# Player_Module.net
KiCad netlist of a schematic drawn in EAGLE
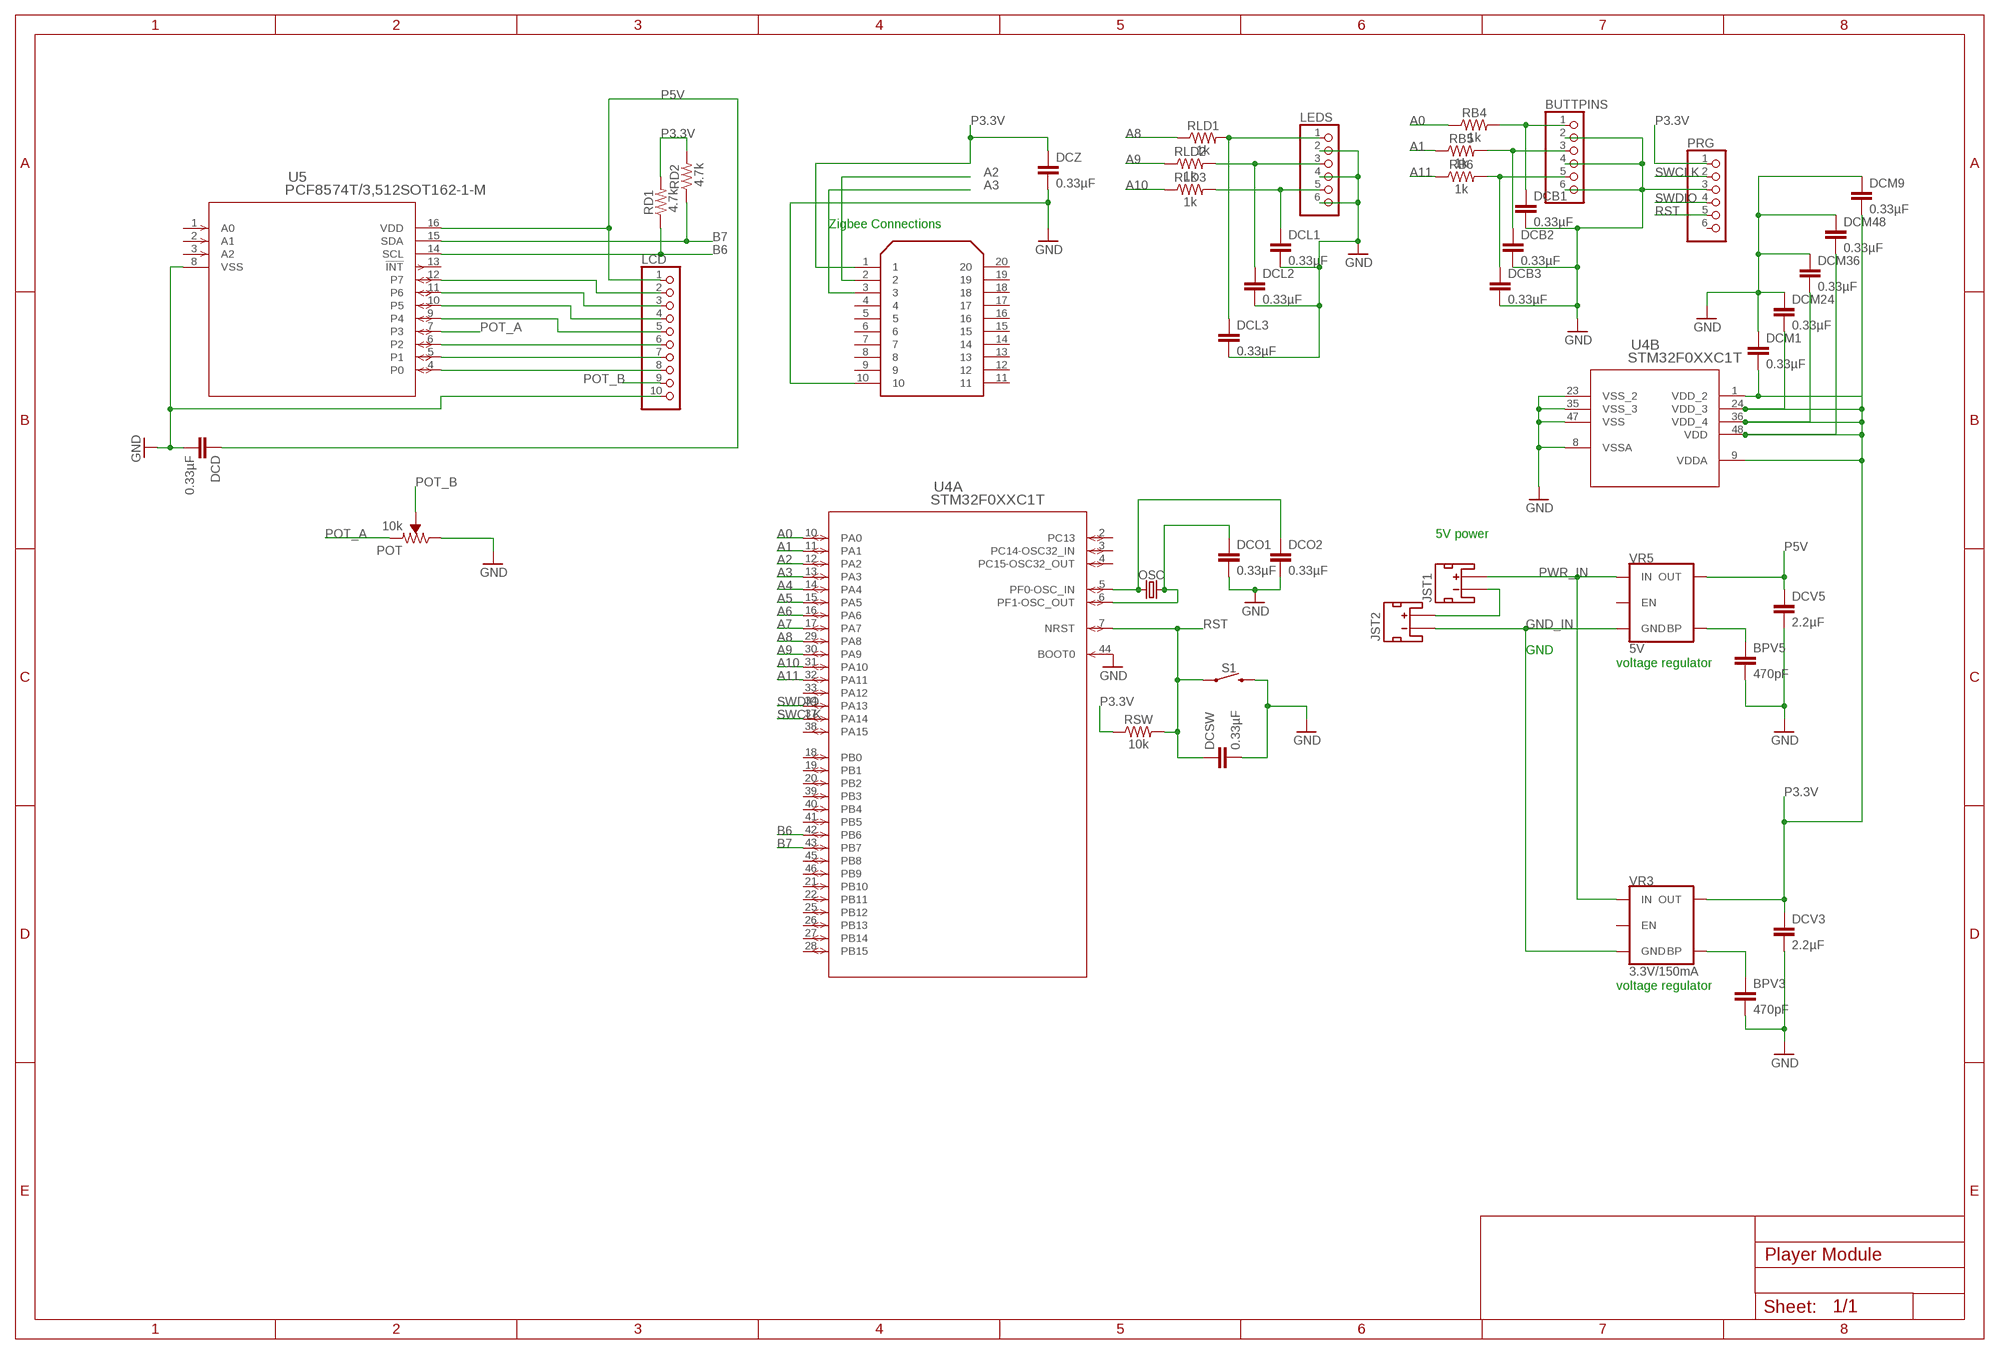
[diagram p0: schematic, sheet 1]

(export (version "E")
  (design (tool "Eeschema 10.0.6"))
  (components
    (comp (ref "BPV3")
      (value "470pF")
      (footprint "eagle-import:0805")
      (libsource (lib "eagle-import") (part "0.33UF/330NF-0805-50V-10%"))
    )
    (comp (ref "BPV5")
      (value "470pF")
      (footprint "eagle-import:0805")
      (libsource (lib "eagle-import") (part "0.33UF/330NF-0805-50V-10%"))
    )
    (comp (ref "BUTTPINS")
      (value "PINHD-1X6")
      (footprint "eagle-import:1X06")
      (libsource (lib "eagle-import") (part "PINHD-1X6"))
    )
    (comp (ref "DCB1")
      (value "0.33µF")
      (footprint "eagle-import:0805")
      (libsource (lib "eagle-import") (part "0.33UF/330NF-0805-50V-10%"))
    )
    (comp (ref "DCB2")
      (value "0.33µF")
      (footprint "eagle-import:0805")
      (libsource (lib "eagle-import") (part "0.33UF/330NF-0805-50V-10%"))
    )
    (comp (ref "DCB3")
      (value "0.33µF")
      (footprint "eagle-import:0805")
      (libsource (lib "eagle-import") (part "0.33UF/330NF-0805-50V-10%"))
    )
    (comp (ref "DCD")
      (value "0.33µF")
      (footprint "eagle-import:0805")
      (libsource (lib "eagle-import") (part "0.33UF/330NF-0805-50V-10%"))
    )
    (comp (ref "DCL1")
      (value "0.33µF")
      (footprint "eagle-import:0805")
      (libsource (lib "eagle-import") (part "0.33UF/330NF-0805-50V-10%"))
    )
    (comp (ref "DCL2")
      (value "0.33µF")
      (footprint "eagle-import:0805")
      (libsource (lib "eagle-import") (part "0.33UF/330NF-0805-50V-10%"))
    )
    (comp (ref "DCL3")
      (value "0.33µF")
      (footprint "eagle-import:0805")
      (libsource (lib "eagle-import") (part "0.33UF/330NF-0805-50V-10%"))
    )
    (comp (ref "DCM1")
      (value "0.33µF")
      (footprint "eagle-import:0805")
      (libsource (lib "eagle-import") (part "0.33UF/330NF-0805-50V-10%"))
    )
    (comp (ref "DCM9")
      (value "0.33µF")
      (footprint "eagle-import:0805")
      (libsource (lib "eagle-import") (part "0.33UF/330NF-0805-50V-10%"))
    )
    (comp (ref "DCM24")
      (value "0.33µF")
      (footprint "eagle-import:0805")
      (libsource (lib "eagle-import") (part "0.33UF/330NF-0805-50V-10%"))
    )
    (comp (ref "DCM36")
      (value "0.33µF")
      (footprint "eagle-import:0805")
      (libsource (lib "eagle-import") (part "0.33UF/330NF-0805-50V-10%"))
    )
    (comp (ref "DCM48")
      (value "0.33µF")
      (footprint "eagle-import:0805")
      (libsource (lib "eagle-import") (part "0.33UF/330NF-0805-50V-10%"))
    )
    (comp (ref "DCO1")
      (value "0.33µF")
      (footprint "eagle-import:0805")
      (libsource (lib "eagle-import") (part "0.33UF/330NF-0805-50V-10%"))
    )
    (comp (ref "DCO2")
      (value "0.33µF")
      (footprint "eagle-import:0805")
      (libsource (lib "eagle-import") (part "0.33UF/330NF-0805-50V-10%"))
    )
    (comp (ref "DCSW")
      (value "0.33µF")
      (footprint "eagle-import:0805")
      (libsource (lib "eagle-import") (part "0.33UF/330NF-0805-50V-10%"))
    )
    (comp (ref "DCV3")
      (value "2.2µF")
      (footprint "eagle-import:0805")
      (libsource (lib "eagle-import") (part "0.33UF/330NF-0805-50V-10%"))
    )
    (comp (ref "DCV5")
      (value "2.2µF")
      (footprint "eagle-import:0805")
      (libsource (lib "eagle-import") (part "0.33UF/330NF-0805-50V-10%"))
    )
    (comp (ref "DCZ")
      (value "0.33µF")
      (footprint "eagle-import:0805")
      (libsource (lib "eagle-import") (part "0.33UF/330NF-0805-50V-10%"))
    )
    (comp (ref "JST1")
      (value "JST_2MM_MALE")
      (footprint "eagle-import:JST-2-SMD")
      (libsource (lib "eagle-import") (part "JST_2MM_MALE"))
    )
    (comp (ref "JST2")
      (value "JST_2MM_MALE")
      (footprint "eagle-import:JST-2-SMD")
      (libsource (lib "eagle-import") (part "JST_2MM_MALE"))
    )
    (comp (ref "LCD")
      (value "PINHD-1X10")
      (footprint "eagle-import:1X10")
      (libsource (lib "eagle-import") (part "PINHD-1X10"))
    )
    (comp (ref "LEDS")
      (value "PINHD-1X6")
      (footprint "eagle-import:1X06")
      (libsource (lib "eagle-import") (part "PINHD-1X6"))
    )
    (comp (ref "OSC")
      (value "CRYSTALPTH-HC49US")
      (footprint "eagle-import:HC49US")
      (libsource (lib "eagle-import") (part "CRYSTALPTH-HC49US"))
    )
    (comp (ref "POT")
      (value "10k")
      (footprint "eagle-import:TRIMPOT-PTH-3386U")
      (libsource (lib "eagle-import") (part "TRIMPOT-PTH-10MM-KNOB-1/2W-10%"))
    )
    (comp (ref "PRG")
      (value "PINHD-1X6")
      (footprint "eagle-import:1X06")
      (libsource (lib "eagle-import") (part "PINHD-1X6"))
    )
    (comp (ref "RB4")
      (value "1k")
      (footprint "eagle-import:0805")
      (libsource (lib "eagle-import") (part "RESISTOR0805"))
    )
    (comp (ref "RB5")
      (value "1k")
      (footprint "eagle-import:0805")
      (libsource (lib "eagle-import") (part "RESISTOR0805"))
    )
    (comp (ref "RB6")
      (value "1k")
      (footprint "eagle-import:0805")
      (libsource (lib "eagle-import") (part "RESISTOR0805"))
    )
    (comp (ref "RD1")
      (value "4.7k")
      (footprint "eagle-import:0805")
      (libsource (lib "eagle-import") (part "RESISTOR0805"))
    )
    (comp (ref "RD2")
      (value "4.7k")
      (footprint "eagle-import:0805")
      (libsource (lib "eagle-import") (part "RESISTOR0805"))
    )
    (comp (ref "RLD1")
      (value "1k")
      (footprint "eagle-import:0805")
      (libsource (lib "eagle-import") (part "RESISTOR0805"))
    )
    (comp (ref "RLD2")
      (value "1k")
      (footprint "eagle-import:0805")
      (libsource (lib "eagle-import") (part "RESISTOR0805"))
    )
    (comp (ref "RLD3")
      (value "1k")
      (footprint "eagle-import:0805")
      (libsource (lib "eagle-import") (part "RESISTOR0805"))
    )
    (comp (ref "RSW")
      (value "10k")
      (footprint "eagle-import:0805")
      (libsource (lib "eagle-import") (part "RESISTOR0805"))
    )
    (comp (ref "S1")
      (value "MOMENTARY-SWITCH-SPST-SMD-5.2MM")
      (footprint "eagle-import:TACTILE_SWITCH_SMD_5.2MM")
      (libsource (lib "eagle-import") (part "MOMENTARY-SWITCH-SPST-SMD-5.2MM"))
    )
    (comp (ref "U$1")
      (value "XB24-BPIT-004")
      (footprint "eagle-import:DIP-20")
      (fields (field (name "MF") "Digi International"))
      (libsource (lib "eagle-import") (part "XB24-BPIT-004"))
    )
    (comp (ref "U4")
      (value "STM32F0XXC1T")
      (footprint "eagle-import:LQFP48-7X7MM")
      (fields (field (name "MANUFACTURER_PART_NUMBER") "stm32f0xxc1t"))
      (libsource (lib "eagle-import") (part "STM32F0XXC1T"))
    )
    (comp (ref "U5")
      (value "PCF8574T/3,512SOT162-1-M")
      (footprint "eagle-import:SOT162-1-M")
      (fields (field (name "MANUFACTURER_PART_NUMBER") "PCF8574T3512"))
      (libsource (lib "eagle-import") (part "PCF8574T/3,512SOT162-1-M"))
    )
    (comp (ref "VR3")
      (value "3.3V/150mA")
      (footprint "eagle-import:SOT23-5")
      (libsource (lib "eagle-import") (part "V_REG_MIC52053.3V"))
    )
    (comp (ref "VR5")
      (value "5V")
      (footprint "eagle-import:SOT23-5")
      (libsource (lib "eagle-import") (part "V_REG_MIC52055V"))
    )
  )
  (nets
    (net (code "1") (name "/A0") (class "Default")
      (node (ref "RB4") (pin "1") (pinfunction "1_1") (pintype "passive"))
      (node (ref "U4") (pin "10") (pinfunction "PA0_10") (pintype "bidirectional"))
    )
    (net (code "2") (name "/A1") (class "Default")
      (node (ref "RB5") (pin "1") (pinfunction "1_1") (pintype "passive"))
      (node (ref "U4") (pin "11") (pinfunction "PA1_11") (pintype "bidirectional"))
    )
    (net (code "3") (name "/A2") (class "Default")
      (node (ref "U$1") (pin "2") (pinfunction "2_2") (pintype "bidirectional"))
      (node (ref "U4") (pin "12") (pinfunction "PA2_12") (pintype "bidirectional"))
    )
    (net (code "4") (name "/A3") (class "Default")
      (node (ref "U$1") (pin "3") (pinfunction "3_3") (pintype "bidirectional"))
      (node (ref "U4") (pin "13") (pinfunction "PA3_13") (pintype "bidirectional"))
    )
    (net (code "5") (name "/A4") (class "Default")
      (node (ref "U4") (pin "14") (pinfunction "PA4_14") (pintype "bidirectional"))
    )
    (net (code "6") (name "/A5") (class "Default")
      (node (ref "U4") (pin "15") (pinfunction "PA5_15") (pintype "bidirectional"))
    )
    (net (code "7") (name "/A6") (class "Default")
      (node (ref "U4") (pin "16") (pinfunction "PA6_16") (pintype "bidirectional"))
    )
    (net (code "8") (name "/A7") (class "Default")
      (node (ref "U4") (pin "17") (pinfunction "PA7_17") (pintype "bidirectional"))
    )
    (net (code "9") (name "/A8") (class "Default")
      (node (ref "RLD1") (pin "1") (pinfunction "1_1") (pintype "passive"))
      (node (ref "U4") (pin "29") (pinfunction "PA8_29") (pintype "bidirectional"))
    )
    (net (code "10") (name "/A9") (class "Default")
      (node (ref "RLD2") (pin "1") (pinfunction "1_1") (pintype "passive"))
      (node (ref "U4") (pin "30") (pinfunction "PA9_30") (pintype "bidirectional"))
    )
    (net (code "11") (name "/A10") (class "Default")
      (node (ref "RLD3") (pin "1") (pinfunction "1_1") (pintype "passive"))
      (node (ref "U4") (pin "31") (pinfunction "PA10_31") (pintype "bidirectional"))
    )
    (net (code "12") (name "/A11") (class "Default")
      (node (ref "RB6") (pin "1") (pinfunction "1_1") (pintype "passive"))
      (node (ref "U4") (pin "32") (pinfunction "PA11_32") (pintype "bidirectional"))
    )
    (net (code "13") (name "/B6") (class "Default")
      (node (ref "RD1") (pin "1") (pinfunction "1_1") (pintype "passive"))
      (node (ref "U4") (pin "42") (pinfunction "PB6_42") (pintype "bidirectional"))
      (node (ref "U5") (pin "14") (pinfunction "SCL_14") (pintype "passive"))
    )
    (net (code "14") (name "/B7") (class "Default")
      (node (ref "RD2") (pin "1") (pinfunction "1_1") (pintype "passive"))
      (node (ref "U4") (pin "43") (pinfunction "PB7_43") (pintype "bidirectional"))
      (node (ref "U5") (pin "15") (pinfunction "SDA_15") (pintype "passive"))
    )
    (net (code "15") (name "/GND_IN") (class "Default")
      (node (ref "JST2") (pin "1") (pinfunction "-_1") (pintype "bidirectional"))
      (node (ref "VR3") (pin "2") (pinfunction "GND_2") (pintype "input"))
      (node (ref "VR5") (pin "2") (pinfunction "GND_2") (pintype "input"))
    )
    (net (code "16") (name "/P3.3V") (class "Default")
      (node (ref "DCM1") (pin "2") (pinfunction "2_2") (pintype "passive"))
      (node (ref "DCM24") (pin "2") (pinfunction "2_2") (pintype "passive"))
      (node (ref "DCM36") (pin "2") (pinfunction "2_2") (pintype "passive"))
      (node (ref "DCM48") (pin "2") (pinfunction "2_2") (pintype "passive"))
      (node (ref "DCM9") (pin "2") (pinfunction "2_2") (pintype "passive"))
      (node (ref "DCV3") (pin "1") (pinfunction "1_1") (pintype "passive"))
      (node (ref "DCZ") (pin "1") (pinfunction "1_1") (pintype "passive"))
      (node (ref "PRG") (pin "1") (pinfunction "1_1") (pintype "passive"))
      (node (ref "RD1") (pin "2") (pinfunction "2_2") (pintype "passive"))
      (node (ref "RD2") (pin "2") (pinfunction "2_2") (pintype "passive"))
      (node (ref "RSW") (pin "1") (pinfunction "1_1") (pintype "passive"))
      (node (ref "U$1") (pin "1") (pinfunction "1_1") (pintype "bidirectional"))
      (node (ref "U4") (pin "1") (pinfunction "VDD_2_1") (pintype "power_in"))
      (node (ref "U4") (pin "24") (pinfunction "VDD_3_24") (pintype "power_in"))
      (node (ref "U4") (pin "36") (pinfunction "VDD_4_36") (pintype "power_in"))
      (node (ref "U4") (pin "48") (pinfunction "VDD_48") (pintype "power_in"))
      (node (ref "U4") (pin "9") (pinfunction "VDDA_9") (pintype "power_in"))
      (node (ref "VR3") (pin "5") (pinfunction "OUT_5") (pintype "passive"))
    )
    (net (code "17") (name "/P5V") (class "Default")
      (node (ref "DCD") (pin "1") (pinfunction "1_1") (pintype "passive"))
      (node (ref "DCV5") (pin "1") (pinfunction "1_1") (pintype "passive"))
      (node (ref "LCD") (pin "1") (pinfunction "1_1") (pintype "passive"))
      (node (ref "U5") (pin "16") (pinfunction "VDD_16") (pintype "power_in"))
      (node (ref "VR5") (pin "5") (pinfunction "OUT_5") (pintype "passive"))
    )
    (net (code "18") (name "/POT_A") (class "Default")
      (node (ref "POT") (pin "1") (pinfunction "CCW_1") (pintype "passive"))
      (node (ref "U5") (pin "7") (pinfunction "P3_7") (pintype "bidirectional"))
    )
    (net (code "19") (name "/POT_B") (class "Default")
      (node (ref "LCD") (pin "9") (pinfunction "9_9") (pintype "passive"))
      (node (ref "POT") (pin "2") (pinfunction "WIPER_2") (pintype "passive"))
    )
    (net (code "20") (name "/PWR_IN") (class "Default")
      (node (ref "JST1") (pin "2") (pinfunction "+_2") (pintype "bidirectional"))
      (node (ref "VR3") (pin "1") (pinfunction "IN_1") (pintype "input"))
      (node (ref "VR5") (pin "1") (pinfunction "IN_1") (pintype "input"))
    )
    (net (code "21") (name "/RST") (class "Default")
      (node (ref "DCSW") (pin "1") (pinfunction "1_1") (pintype "passive"))
      (node (ref "PRG") (pin "5") (pinfunction "5_5") (pintype "passive"))
      (node (ref "RSW") (pin "2") (pinfunction "2_2") (pintype "passive"))
      (node (ref "S1") (pin "1") (pinfunction "1_1") (pintype "passive"))
      (node (ref "U4") (pin "7") (pinfunction "NRST_7") (pintype "bidirectional"))
    )
    (net (code "22") (name "/SWCLK") (class "Default")
      (node (ref "PRG") (pin "2") (pinfunction "2_2") (pintype "passive"))
      (node (ref "U4") (pin "37") (pinfunction "PA14_37") (pintype "bidirectional"))
    )
    (net (code "23") (name "/SWDIO") (class "Default")
      (node (ref "PRG") (pin "4") (pinfunction "4_4") (pintype "passive"))
      (node (ref "U4") (pin "34") (pinfunction "PA13_34") (pintype "bidirectional"))
    )
    (net (code "24") (name "GND") (class "Default")
      (node (ref "BPV3") (pin "2") (pinfunction "2_2") (pintype "passive"))
      (node (ref "BPV5") (pin "2") (pinfunction "2_2") (pintype "passive"))
      (node (ref "BUTTPINS") (pin "2") (pinfunction "2_2") (pintype "passive"))
      (node (ref "BUTTPINS") (pin "4") (pinfunction "4_4") (pintype "passive"))
      (node (ref "BUTTPINS") (pin "6") (pinfunction "6_6") (pintype "passive"))
      (node (ref "DCB1") (pin "2") (pinfunction "2_2") (pintype "passive"))
      (node (ref "DCB2") (pin "2") (pinfunction "2_2") (pintype "passive"))
      (node (ref "DCB3") (pin "2") (pinfunction "2_2") (pintype "passive"))
      (node (ref "DCD") (pin "2") (pinfunction "2_2") (pintype "passive"))
      (node (ref "DCL1") (pin "2") (pinfunction "2_2") (pintype "passive"))
      (node (ref "DCL2") (pin "2") (pinfunction "2_2") (pintype "passive"))
      (node (ref "DCL3") (pin "2") (pinfunction "2_2") (pintype "passive"))
      (node (ref "DCM1") (pin "1") (pinfunction "1_1") (pintype "passive"))
      (node (ref "DCM24") (pin "1") (pinfunction "1_1") (pintype "passive"))
      (node (ref "DCM36") (pin "1") (pinfunction "1_1") (pintype "passive"))
      (node (ref "DCM48") (pin "1") (pinfunction "1_1") (pintype "passive"))
      (node (ref "DCM9") (pin "1") (pinfunction "1_1") (pintype "passive"))
      (node (ref "DCO1") (pin "2") (pinfunction "2_2") (pintype "passive"))
      (node (ref "DCO2") (pin "2") (pinfunction "2_2") (pintype "passive"))
      (node (ref "DCSW") (pin "2") (pinfunction "2_2") (pintype "passive"))
      (node (ref "DCV3") (pin "2") (pinfunction "2_2") (pintype "passive"))
      (node (ref "DCV5") (pin "2") (pinfunction "2_2") (pintype "passive"))
      (node (ref "DCZ") (pin "2") (pinfunction "2_2") (pintype "passive"))
      (node (ref "LCD") (pin "10") (pinfunction "10_10") (pintype "passive"))
      (node (ref "LEDS") (pin "2") (pinfunction "2_2") (pintype "passive"))
      (node (ref "LEDS") (pin "4") (pinfunction "4_4") (pintype "passive"))
      (node (ref "LEDS") (pin "6") (pinfunction "6_6") (pintype "passive"))
      (node (ref "POT") (pin "3") (pinfunction "CW_3") (pintype "passive"))
      (node (ref "PRG") (pin "3") (pinfunction "3_3") (pintype "passive"))
      (node (ref "S1") (pin "3") (pinfunction "2_3") (pintype "passive"))
      (node (ref "U$1") (pin "10") (pinfunction "10_10") (pintype "bidirectional"))
      (node (ref "U4") (pin "23") (pinfunction "VSS_2_23") (pintype "power_in"))
      (node (ref "U4") (pin "35") (pinfunction "VSS_3_35") (pintype "power_in"))
      (node (ref "U4") (pin "44") (pinfunction "BOOT0_44") (pintype "input"))
      (node (ref "U4") (pin "47") (pinfunction "VSS_47") (pintype "power_in"))
      (node (ref "U4") (pin "8") (pinfunction "VSSA_8") (pintype "power_in"))
      (node (ref "U5") (pin "8") (pinfunction "VSS_8") (pintype "power_in"))
    )
    (net (code "25") (name "Net-(BUTTPINS-Pad1)") (class "Default")
      (node (ref "BUTTPINS") (pin "1") (pinfunction "1_1") (pintype "passive"))
      (node (ref "DCB1") (pin "1") (pinfunction "1_1") (pintype "passive"))
      (node (ref "RB4") (pin "2") (pinfunction "2_2") (pintype "passive"))
    )
    (net (code "26") (name "Net-(BUTTPINS-Pad3)") (class "Default")
      (node (ref "BUTTPINS") (pin "3") (pinfunction "3_3") (pintype "passive"))
      (node (ref "DCB2") (pin "1") (pinfunction "1_1") (pintype "passive"))
      (node (ref "RB5") (pin "2") (pinfunction "2_2") (pintype "passive"))
    )
    (net (code "27") (name "Net-(BUTTPINS-Pad5)") (class "Default")
      (node (ref "BUTTPINS") (pin "5") (pinfunction "5_5") (pintype "passive"))
      (node (ref "DCB3") (pin "1") (pinfunction "1_1") (pintype "passive"))
      (node (ref "RB6") (pin "2") (pinfunction "2_2") (pintype "passive"))
    )
    (net (code "28") (name "Net-(DCL1-Pad1)") (class "Default")
      (node (ref "DCL1") (pin "1") (pinfunction "1_1") (pintype "passive"))
      (node (ref "LEDS") (pin "5") (pinfunction "5_5") (pintype "passive"))
      (node (ref "RLD3") (pin "2") (pinfunction "2_2") (pintype "passive"))
    )
    (net (code "29") (name "Net-(DCL2-Pad1)") (class "Default")
      (node (ref "DCL2") (pin "1") (pinfunction "1_1") (pintype "passive"))
      (node (ref "LEDS") (pin "3") (pinfunction "3_3") (pintype "passive"))
      (node (ref "RLD2") (pin "2") (pinfunction "2_2") (pintype "passive"))
    )
    (net (code "30") (name "Net-(DCL3-Pad1)") (class "Default")
      (node (ref "DCL3") (pin "1") (pinfunction "1_1") (pintype "passive"))
      (node (ref "LEDS") (pin "1") (pinfunction "1_1") (pintype "passive"))
      (node (ref "RLD1") (pin "2") (pinfunction "2_2") (pintype "passive"))
    )
    (net (code "31") (name "Net-(JST1--)") (class "Default")
      (node (ref "JST1") (pin "1") (pinfunction "-_1") (pintype "bidirectional"))
      (node (ref "JST2") (pin "2") (pinfunction "+_2") (pintype "bidirectional"))
    )
    (net (code "32") (name "Net-(U4A-PF0-OSC_IN)") (class "Default")
      (node (ref "DCO2") (pin "1") (pinfunction "1_1") (pintype "passive"))
      (node (ref "OSC") (pin "1") (pinfunction "1_1") (pintype "passive"))
      (node (ref "U4") (pin "5") (pinfunction "PF0-OSC_IN_5") (pintype "bidirectional"))
    )
    (net (code "33") (name "Net-(U4A-PF1-OSC_OUT)") (class "Default")
      (node (ref "DCO1") (pin "1") (pinfunction "1_1") (pintype "passive"))
      (node (ref "OSC") (pin "2") (pinfunction "2_2") (pintype "passive"))
      (node (ref "U4") (pin "6") (pinfunction "PF1-OSC_OUT_6") (pintype "bidirectional"))
    )
    (net (code "34") (name "Net-(U5-P0)") (class "Default")
      (node (ref "LCD") (pin "8") (pinfunction "8_8") (pintype "passive"))
      (node (ref "U5") (pin "4") (pinfunction "P0_4") (pintype "bidirectional"))
    )
    (net (code "35") (name "Net-(U5-P1)") (class "Default")
      (node (ref "LCD") (pin "7") (pinfunction "7_7") (pintype "passive"))
      (node (ref "U5") (pin "5") (pinfunction "P1_5") (pintype "bidirectional"))
    )
    (net (code "36") (name "Net-(U5-P2)") (class "Default")
      (node (ref "LCD") (pin "6") (pinfunction "6_6") (pintype "passive"))
      (node (ref "U5") (pin "6") (pinfunction "P2_6") (pintype "bidirectional"))
    )
    (net (code "37") (name "Net-(U5-P4)") (class "Default")
      (node (ref "LCD") (pin "5") (pinfunction "5_5") (pintype "passive"))
      (node (ref "U5") (pin "9") (pinfunction "P4_9") (pintype "bidirectional"))
    )
    (net (code "38") (name "Net-(U5-P5)") (class "Default")
      (node (ref "LCD") (pin "4") (pinfunction "4_4") (pintype "passive"))
      (node (ref "U5") (pin "10") (pinfunction "P5_10") (pintype "bidirectional"))
    )
    (net (code "39") (name "Net-(U5-P6)") (class "Default")
      (node (ref "LCD") (pin "3") (pinfunction "3_3") (pintype "passive"))
      (node (ref "U5") (pin "11") (pinfunction "P6_11") (pintype "bidirectional"))
    )
    (net (code "40") (name "Net-(U5-P7)") (class "Default")
      (node (ref "LCD") (pin "2") (pinfunction "2_2") (pintype "passive"))
      (node (ref "U5") (pin "12") (pinfunction "P7_12") (pintype "bidirectional"))
    )
    (net (code "41") (name "Net-(VR3-BP)") (class "Default")
      (node (ref "BPV3") (pin "1") (pinfunction "1_1") (pintype "passive"))
      (node (ref "VR3") (pin "4") (pinfunction "BP_4") (pintype "input"))
    )
    (net (code "42") (name "Net-(VR5-BP)") (class "Default")
      (node (ref "BPV5") (pin "1") (pinfunction "1_1") (pintype "passive"))
      (node (ref "VR5") (pin "4") (pinfunction "BP_4") (pintype "input"))
    )
    (net (code "43") (name "unconnected-(JST1-PAD1-PadNC1)") (class "Default")
      (node (ref "JST1") (pin "NC1") (pinfunction "PAD1_NC1") (pintype "bidirectional"))
    )
    (net (code "44") (name "unconnected-(JST1-PAD2-PadNC2)") (class "Default")
      (node (ref "JST1") (pin "NC2") (pinfunction "PAD2_NC2") (pintype "bidirectional"))
    )
    (net (code "45") (name "unconnected-(JST2-PAD1-PadNC1)") (class "Default")
      (node (ref "JST2") (pin "NC1") (pinfunction "PAD1_NC1") (pintype "bidirectional"))
    )
    (net (code "46") (name "unconnected-(JST2-PAD2-PadNC2)") (class "Default")
      (node (ref "JST2") (pin "NC2") (pinfunction "PAD2_NC2") (pintype "bidirectional"))
    )
    (net (code "47") (name "unconnected-(PRG-Pad6)") (class "Default")
      (node (ref "PRG") (pin "6") (pinfunction "6_6") (pintype "passive"))
    )
    (net (code "48") (name "unconnected-(U$1-Pad4)") (class "Default")
      (node (ref "U$1") (pin "4") (pinfunction "4_4") (pintype "bidirectional"))
    )
    (net (code "49") (name "unconnected-(U$1-Pad5)") (class "Default")
      (node (ref "U$1") (pin "5") (pinfunction "5_5") (pintype "bidirectional"))
    )
    (net (code "50") (name "unconnected-(U$1-Pad6)") (class "Default")
      (node (ref "U$1") (pin "6") (pinfunction "6_6") (pintype "bidirectional"))
    )
    (net (code "51") (name "unconnected-(U$1-Pad7)") (class "Default")
      (node (ref "U$1") (pin "7") (pinfunction "7_7") (pintype "bidirectional"))
    )
    (net (code "52") (name "unconnected-(U$1-Pad8)") (class "Default")
      (node (ref "U$1") (pin "8") (pinfunction "8_8") (pintype "bidirectional"))
    )
    (net (code "53") (name "unconnected-(U$1-Pad9)") (class "Default")
      (node (ref "U$1") (pin "9") (pinfunction "9_9") (pintype "bidirectional"))
    )
    (net (code "54") (name "unconnected-(U$1-Pad11)") (class "Default")
      (node (ref "U$1") (pin "11") (pinfunction "11_11") (pintype "bidirectional"))
    )
    (net (code "55") (name "unconnected-(U$1-Pad12)") (class "Default")
      (node (ref "U$1") (pin "12") (pinfunction "12_12") (pintype "bidirectional"))
    )
    (net (code "56") (name "unconnected-(U$1-Pad13)") (class "Default")
      (node (ref "U$1") (pin "13") (pinfunction "13_13") (pintype "bidirectional"))
    )
    (net (code "57") (name "unconnected-(U$1-Pad14)") (class "Default")
      (node (ref "U$1") (pin "14") (pinfunction "14_14") (pintype "bidirectional"))
    )
    (net (code "58") (name "unconnected-(U$1-Pad15)") (class "Default")
      (node (ref "U$1") (pin "15") (pinfunction "15_15") (pintype "bidirectional"))
    )
    (net (code "59") (name "unconnected-(U$1-Pad16)") (class "Default")
      (node (ref "U$1") (pin "16") (pinfunction "16_16") (pintype "bidirectional"))
    )
    (net (code "60") (name "unconnected-(U$1-Pad17)") (class "Default")
      (node (ref "U$1") (pin "17") (pinfunction "17_17") (pintype "bidirectional"))
    )
    (net (code "61") (name "unconnected-(U$1-Pad18)") (class "Default")
      (node (ref "U$1") (pin "18") (pinfunction "18_18") (pintype "bidirectional"))
    )
    (net (code "62") (name "unconnected-(U$1-Pad19)") (class "Default")
      (node (ref "U$1") (pin "19") (pinfunction "19_19") (pintype "bidirectional"))
    )
    (net (code "63") (name "unconnected-(U$1-Pad20)") (class "Default")
      (node (ref "U$1") (pin "20") (pinfunction "20_20") (pintype "bidirectional"))
    )
    (net (code "64") (name "unconnected-(U4A-PA12-Pad33)") (class "Default")
      (node (ref "U4") (pin "33") (pinfunction "PA12_33") (pintype "bidirectional"))
    )
    (net (code "65") (name "unconnected-(U4A-PA15-Pad38)") (class "Default")
      (node (ref "U4") (pin "38") (pinfunction "PA15_38") (pintype "bidirectional"))
    )
    (net (code "66") (name "unconnected-(U4A-PB0-Pad18)") (class "Default")
      (node (ref "U4") (pin "18") (pinfunction "PB0_18") (pintype "bidirectional"))
    )
    (net (code "67") (name "unconnected-(U4A-PB1-Pad19)") (class "Default")
      (node (ref "U4") (pin "19") (pinfunction "PB1_19") (pintype "bidirectional"))
    )
    (net (code "68") (name "unconnected-(U4A-PB2-Pad20)") (class "Default")
      (node (ref "U4") (pin "20") (pinfunction "PB2_20") (pintype "bidirectional"))
    )
    (net (code "69") (name "unconnected-(U4A-PB3-Pad39)") (class "Default")
      (node (ref "U4") (pin "39") (pinfunction "PB3_39") (pintype "bidirectional"))
    )
    (net (code "70") (name "unconnected-(U4A-PB4-Pad40)") (class "Default")
      (node (ref "U4") (pin "40") (pinfunction "PB4_40") (pintype "bidirectional"))
    )
    (net (code "71") (name "unconnected-(U4A-PB5-Pad41)") (class "Default")
      (node (ref "U4") (pin "41") (pinfunction "PB5_41") (pintype "bidirectional"))
    )
    (net (code "72") (name "unconnected-(U4A-PB8-Pad45)") (class "Default")
      (node (ref "U4") (pin "45") (pinfunction "PB8_45") (pintype "bidirectional"))
    )
    (net (code "73") (name "unconnected-(U4A-PB9-Pad46)") (class "Default")
      (node (ref "U4") (pin "46") (pinfunction "PB9_46") (pintype "bidirectional"))
    )
    (net (code "74") (name "unconnected-(U4A-PB10-Pad21)") (class "Default")
      (node (ref "U4") (pin "21") (pinfunction "PB10_21") (pintype "bidirectional"))
    )
    (net (code "75") (name "unconnected-(U4A-PB11-Pad22)") (class "Default")
      (node (ref "U4") (pin "22") (pinfunction "PB11_22") (pintype "bidirectional"))
    )
    (net (code "76") (name "unconnected-(U4A-PB12-Pad25)") (class "Default")
      (node (ref "U4") (pin "25") (pinfunction "PB12_25") (pintype "bidirectional"))
    )
    (net (code "77") (name "unconnected-(U4A-PB13-Pad26)") (class "Default")
      (node (ref "U4") (pin "26") (pinfunction "PB13_26") (pintype "bidirectional"))
    )
    (net (code "78") (name "unconnected-(U4A-PB14-Pad27)") (class "Default")
      (node (ref "U4") (pin "27") (pinfunction "PB14_27") (pintype "bidirectional"))
    )
    (net (code "79") (name "unconnected-(U4A-PB15-Pad28)") (class "Default")
      (node (ref "U4") (pin "28") (pinfunction "PB15_28") (pintype "bidirectional"))
    )
    (net (code "80") (name "unconnected-(U4A-PC13-Pad2)") (class "Default")
      (node (ref "U4") (pin "2") (pinfunction "PC13_2") (pintype "bidirectional"))
    )
    (net (code "81") (name "unconnected-(U4A-PC14-OSC32_IN-Pad3)") (class "Default")
      (node (ref "U4") (pin "3") (pinfunction "PC14-OSC32_IN_3") (pintype "bidirectional"))
    )
    (net (code "82") (name "unconnected-(U4A-PC15-OSC32_OUT-Pad4)") (class "Default")
      (node (ref "U4") (pin "4") (pinfunction "PC15-OSC32_OUT_4") (pintype "bidirectional"))
    )
    (net (code "83") (name "unconnected-(U5-A0-Pad1)") (class "Default")
      (node (ref "U5") (pin "1") (pinfunction "A0_1") (pintype "input"))
    )
    (net (code "84") (name "unconnected-(U5-A1-Pad2)") (class "Default")
      (node (ref "U5") (pin "2") (pinfunction "A1_2") (pintype "input"))
    )
    (net (code "85") (name "unconnected-(U5-A2-Pad3)") (class "Default")
      (node (ref "U5") (pin "3") (pinfunction "A2_3") (pintype "input"))
    )
    (net (code "86") (name "unconnected-(U5-~{INT}-Pad13)") (class "Default")
      (node (ref "U5") (pin "13") (pinfunction "~{INT}_13") (pintype "output"))
    )
    (net (code "87") (name "unconnected-(VR3-EN-Pad3)") (class "Default")
      (node (ref "VR3") (pin "3") (pinfunction "EN_3") (pintype "input"))
    )
    (net (code "88") (name "unconnected-(VR5-EN-Pad3)") (class "Default")
      (node (ref "VR5") (pin "3") (pinfunction "EN_3") (pintype "input"))
    )
  )
)
